# SimGEKI2_Switches.net
KiCad netlist of a schematic drawn in EasyEDA Pro
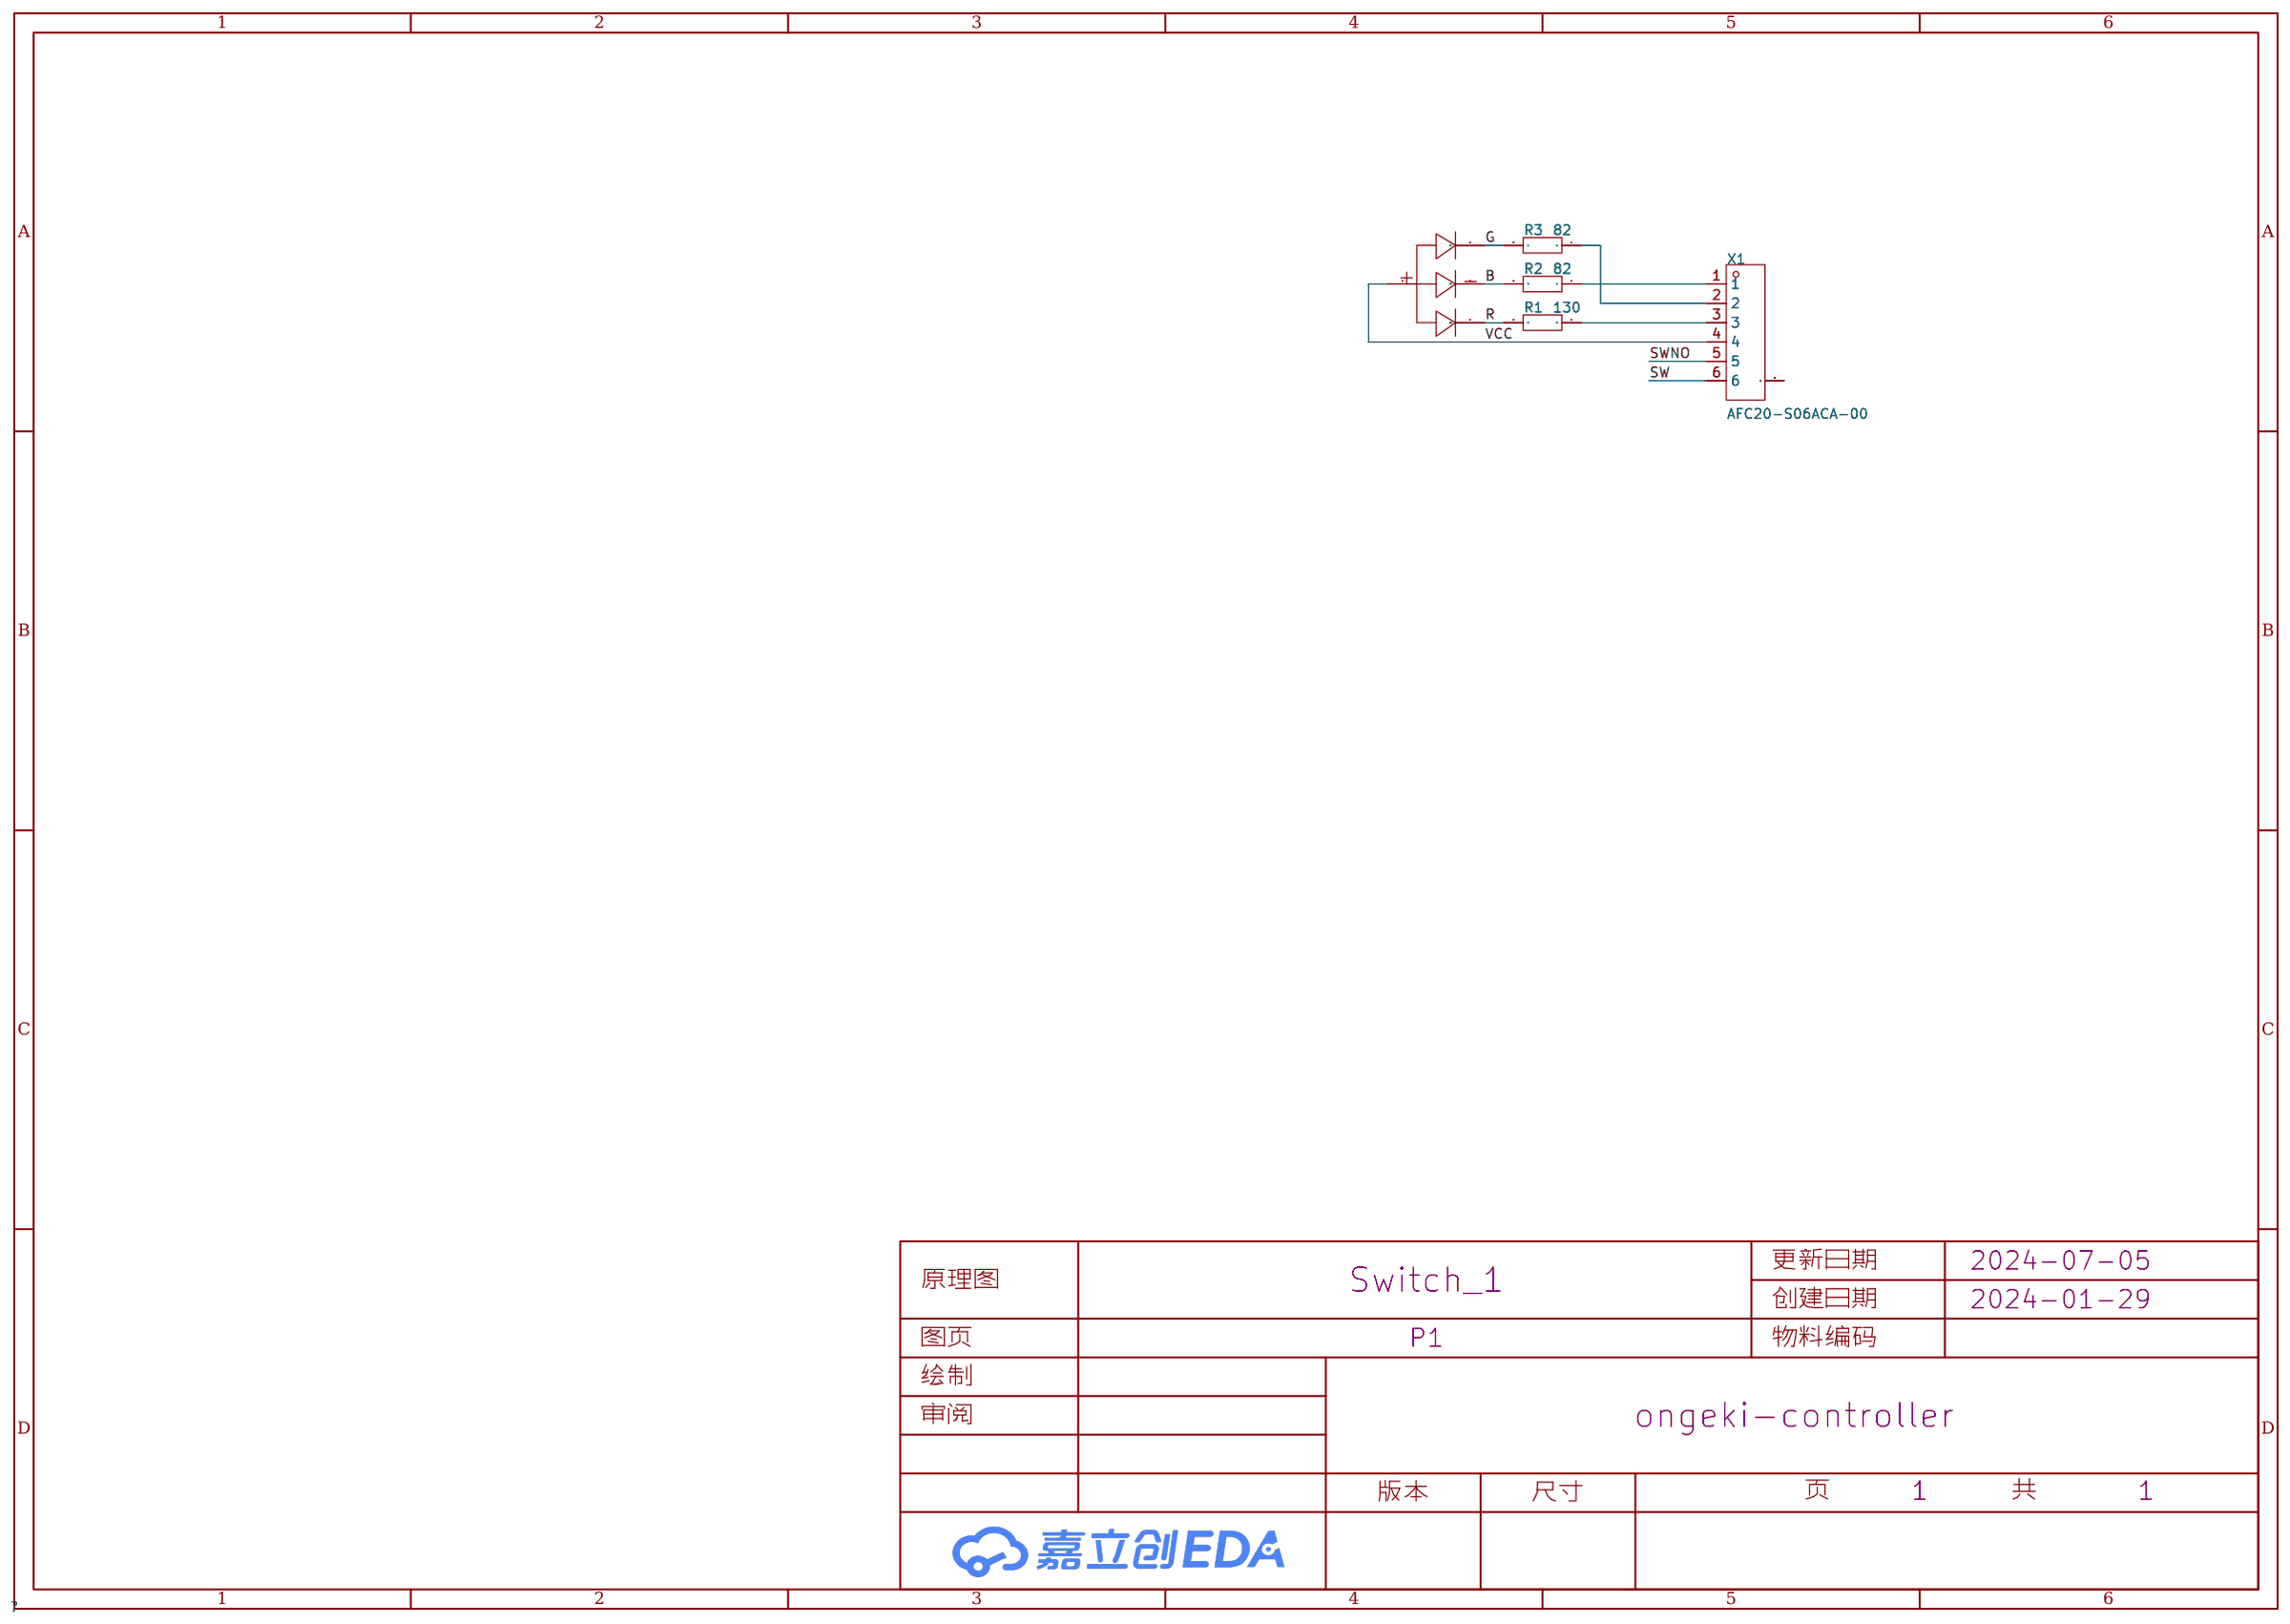
[diagram p0: schematic sheet]

(export (version "E")
  (design (tool "Eeschema 10.0.6"))
  (components
    (comp (ref "LED")
      (value "~")
      (footprint "easyedapro:LED-SMD_4P-L4.0-W1.7-P0.84_C9900049198")
      (libsource (lib "easyedapro") (part "4020侧贴共阳RGB"))
    )
    (comp (ref "R1") (value "130") (footprint "easyedapro:R0603") (libsource (lib "easyedapro") (part "电阻")))
    (comp (ref "R2") (value "82") (footprint "easyedapro:R0603") (libsource (lib "easyedapro") (part "电阻")))
    (comp (ref "R3") (value "82") (footprint "easyedapro:R0603") (libsource (lib "easyedapro") (part "电阻")))
    (comp (ref "X1")
      (value "AFC20-S06ACA-00")
      (footprint "easyedapro:CONN-SMD_6P-P2.00-H-AFC20-S06ACA-00")
      (description "插针结构:1x6P;间距:2mm;公母:公;安装方式:卧贴;行距:-;排数:1;每排PIN数:6;参考系列:PH;额定电流:2A;工作温度范围:-20°C~+85°C;")
      (fields (field (name "Manufacturer") "JS(钜硕电子)"))
      (libsource (lib "easyedapro") (part "AFC20-S06ACA-00"))
    )
  )
  (nets
    (net (code "1") (name "/B") (class "Default")
      (node (ref "LED") (pin "2") (pinfunction "C2_2") (pintype "input"))
      (node (ref "R2") (pin "2") (pinfunction "2_2") (pintype "input"))
    )
    (net (code "2") (name "/G") (class "Default")
      (node (ref "LED") (pin "1") (pinfunction "C1_1") (pintype "input"))
      (node (ref "R3") (pin "2") (pinfunction "2_2") (pintype "input"))
    )
    (net (code "3") (name "/R") (class "Default")
      (node (ref "LED") (pin "4") (pinfunction "C3_4") (pintype "input"))
      (node (ref "R1") (pin "2") (pinfunction "2_2") (pintype "input"))
    )
    (net (code "4") (name "/SW") (class "Default")
      (node (ref "X1") (pin "6") (pinfunction "6_6") (pintype "unspecified"))
    )
    (net (code "5") (name "/SWNO") (class "Default")
      (node (ref "X1") (pin "5") (pinfunction "5_5") (pintype "unspecified"))
    )
    (net (code "6") (name "/VCC") (class "Default")
      (node (ref "LED") (pin "3") (pinfunction "A_3") (pintype "input"))
      (node (ref "X1") (pin "4") (pinfunction "4_4") (pintype "unspecified"))
    )
    (net (code "7") (name "Net-(R1-Pad1)") (class "Default")
      (node (ref "R1") (pin "1") (pinfunction "1_1") (pintype "input"))
      (node (ref "X1") (pin "3") (pinfunction "3_3") (pintype "unspecified"))
    )
    (net (code "8") (name "Net-(R2-Pad1)") (class "Default")
      (node (ref "R2") (pin "1") (pinfunction "1_1") (pintype "input"))
      (node (ref "X1") (pin "1") (pinfunction "1_1") (pintype "unspecified"))
    )
    (net (code "9") (name "Net-(R3-Pad1)") (class "Default")
      (node (ref "R3") (pin "1") (pinfunction "1_1") (pintype "input"))
      (node (ref "X1") (pin "2") (pinfunction "2_2") (pintype "unspecified"))
    )
    (net (code "10") (name "unconnected-(X1-Pad0)") (class "Default")
      (node (ref "X1") (pin "0") (pinfunction "0_0") (pintype "unspecified"))
    )
  )
)
